# UNO_Mega_IO.net
KiCad netlist of a schematic drawn in Altium Designer
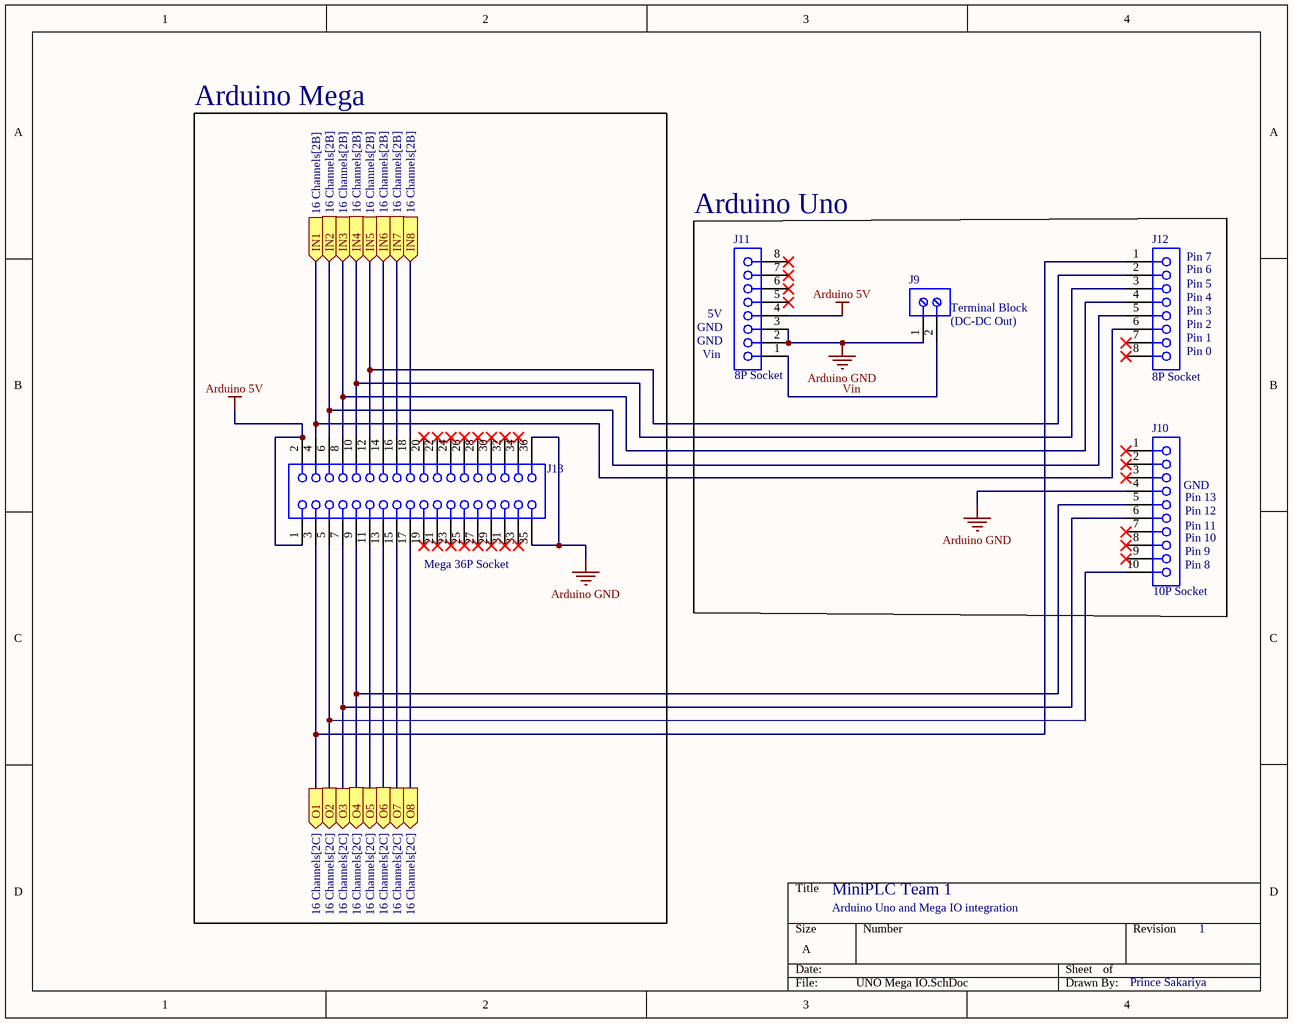
[diagram p0: UNO Mega IO.SchDoc]

(export (version "E")
  (design (tool "Eeschema 10.0.6"))
  (components
    (comp (ref "J9")
      (value "Terminal Block")
      (footprint "691103110002")
      (fields (field (name "VOLTAGE") "125V"))
      (libsource (lib "Altium Content Vault") (part "TBL - 1R - 02P - Screw"))
    )
    (comp (ref "J10")
      (value "10P Socket")
      (footprint "61301011821")
      (libsource (lib "Altium Content Vault") (part "Header_Female_1R_10P"))
    )
    (comp (ref "J11")
      (value "8P Socket")
      (footprint "61300811821")
      (libsource (lib "Altium Content Vault") (part "Header_Female_1R_08P"))
    )
    (comp (ref "J12")
      (value "8P Socket")
      (footprint "61300811821")
      (libsource (lib "Altium Content Vault") (part "Header_Female_1R_08P"))
    )
    (comp (ref "J13")
      (value "Mega 36P Socket")
      (footprint "61303621821")
      (libsource (lib "Altium Content Vault") (part "Header_Female_2R_36P"))
    )
  )
  (nets
    (net (code "1") (name "/IN1") (class "Default")
      (node (ref "J12") (pin "6") (pinfunction "6_6") (pintype "passive"))
      (node (ref "J13") (pin "4") (pinfunction "4_4") (pintype "passive"))
    )
    (net (code "2") (name "/IN2") (class "Default")
      (node (ref "J12") (pin "5") (pinfunction "5_5") (pintype "passive"))
      (node (ref "J13") (pin "6") (pinfunction "6_6") (pintype "passive"))
    )
    (net (code "3") (name "/IN3") (class "Default")
      (node (ref "J12") (pin "4") (pinfunction "4_4") (pintype "passive"))
      (node (ref "J13") (pin "8") (pinfunction "8_8") (pintype "passive"))
    )
    (net (code "4") (name "/IN4") (class "Default")
      (node (ref "J12") (pin "3") (pinfunction "3_3") (pintype "passive"))
      (node (ref "J13") (pin "10") (pinfunction "10_10") (pintype "passive"))
    )
    (net (code "5") (name "/IN5") (class "Default")
      (node (ref "J12") (pin "2") (pinfunction "2_2") (pintype "passive"))
      (node (ref "J13") (pin "12") (pinfunction "12_12") (pintype "passive"))
    )
    (net (code "6") (name "/IN6") (class "Default")
      (node (ref "J13") (pin "14") (pinfunction "14_14") (pintype "passive"))
    )
    (net (code "7") (name "/IN7") (class "Default")
      (node (ref "J13") (pin "16") (pinfunction "16_16") (pintype "passive"))
    )
    (net (code "8") (name "/IN8") (class "Default")
      (node (ref "J13") (pin "18") (pinfunction "18_18") (pintype "passive"))
    )
    (net (code "9") (name "/O1") (class "Default")
      (node (ref "J12") (pin "1") (pinfunction "1_1") (pintype "passive"))
      (node (ref "J13") (pin "3") (pinfunction "3_3") (pintype "passive"))
    )
    (net (code "10") (name "/O2") (class "Default")
      (node (ref "J10") (pin "10") (pinfunction "10_10") (pintype "passive"))
      (node (ref "J13") (pin "5") (pinfunction "5_5") (pintype "passive"))
    )
    (net (code "11") (name "/O3") (class "Default")
      (node (ref "J10") (pin "6") (pinfunction "6_6") (pintype "passive"))
      (node (ref "J13") (pin "7") (pinfunction "7_7") (pintype "passive"))
    )
    (net (code "12") (name "/O4") (class "Default")
      (node (ref "J10") (pin "5") (pinfunction "5_5") (pintype "passive"))
      (node (ref "J13") (pin "9") (pinfunction "9_9") (pintype "passive"))
    )
    (net (code "13") (name "/O5") (class "Default")
      (node (ref "J13") (pin "11") (pinfunction "11_11") (pintype "passive"))
    )
    (net (code "14") (name "/O6") (class "Default")
      (node (ref "J13") (pin "13") (pinfunction "13_13") (pintype "passive"))
    )
    (net (code "15") (name "/O7") (class "Default")
      (node (ref "J13") (pin "15") (pinfunction "15_15") (pintype "passive"))
    )
    (net (code "16") (name "/O8") (class "Default")
      (node (ref "J13") (pin "17") (pinfunction "17_17") (pintype "passive"))
    )
    (net (code "17") (name "/Vin") (class "Default")
      (node (ref "J11") (pin "1") (pinfunction "1_1") (pintype "passive"))
      (node (ref "J9") (pin "2") (pinfunction "2_2") (pintype "passive"))
    )
    (net (code "18") (name "Arduino 5V") (class "Default")
      (node (ref "J11") (pin "4") (pinfunction "4_4") (pintype "passive"))
      (node (ref "J13") (pin "1") (pinfunction "1_1") (pintype "passive"))
      (node (ref "J13") (pin "2") (pinfunction "2_2") (pintype "passive"))
    )
    (net (code "19") (name "Arduino GND") (class "Default")
      (node (ref "J10") (pin "4") (pinfunction "4_4") (pintype "passive"))
      (node (ref "J11") (pin "2") (pinfunction "2_2") (pintype "passive"))
      (node (ref "J11") (pin "3") (pinfunction "3_3") (pintype "passive"))
      (node (ref "J13") (pin "35") (pinfunction "35_35") (pintype "passive"))
      (node (ref "J13") (pin "36") (pinfunction "36_36") (pintype "passive"))
      (node (ref "J9") (pin "1") (pinfunction "1_1") (pintype "passive"))
    )
    (net (code "20") (name "unconnected-(J10-Pad1)") (class "Default")
      (node (ref "J10") (pin "1") (pinfunction "1_1") (pintype "passive+no_connect"))
    )
    (net (code "21") (name "unconnected-(J10-Pad2)") (class "Default")
      (node (ref "J10") (pin "2") (pinfunction "2_2") (pintype "passive+no_connect"))
    )
    (net (code "22") (name "unconnected-(J10-Pad3)") (class "Default")
      (node (ref "J10") (pin "3") (pinfunction "3_3") (pintype "passive+no_connect"))
    )
    (net (code "23") (name "unconnected-(J10-Pad7)") (class "Default")
      (node (ref "J10") (pin "7") (pinfunction "7_7") (pintype "passive+no_connect"))
    )
    (net (code "24") (name "unconnected-(J10-Pad8)") (class "Default")
      (node (ref "J10") (pin "8") (pinfunction "8_8") (pintype "passive+no_connect"))
    )
    (net (code "25") (name "unconnected-(J10-Pad9)") (class "Default")
      (node (ref "J10") (pin "9") (pinfunction "9_9") (pintype "passive+no_connect"))
    )
    (net (code "26") (name "unconnected-(J11-Pad5)") (class "Default")
      (node (ref "J11") (pin "5") (pinfunction "5_5") (pintype "passive+no_connect"))
    )
    (net (code "27") (name "unconnected-(J11-Pad6)") (class "Default")
      (node (ref "J11") (pin "6") (pinfunction "6_6") (pintype "passive+no_connect"))
    )
    (net (code "28") (name "unconnected-(J11-Pad7)") (class "Default")
      (node (ref "J11") (pin "7") (pinfunction "7_7") (pintype "passive+no_connect"))
    )
    (net (code "29") (name "unconnected-(J11-Pad8)") (class "Default")
      (node (ref "J11") (pin "8") (pinfunction "8_8") (pintype "passive+no_connect"))
    )
    (net (code "30") (name "unconnected-(J12-Pad7)") (class "Default")
      (node (ref "J12") (pin "7") (pinfunction "7_7") (pintype "passive+no_connect"))
    )
    (net (code "31") (name "unconnected-(J12-Pad8)") (class "Default")
      (node (ref "J12") (pin "8") (pinfunction "8_8") (pintype "passive+no_connect"))
    )
    (net (code "32") (name "unconnected-(J13-Pad19)") (class "Default")
      (node (ref "J13") (pin "19") (pinfunction "19_19") (pintype "passive+no_connect"))
    )
    (net (code "33") (name "unconnected-(J13-Pad20)") (class "Default")
      (node (ref "J13") (pin "20") (pinfunction "20_20") (pintype "passive+no_connect"))
    )
    (net (code "34") (name "unconnected-(J13-Pad21)") (class "Default")
      (node (ref "J13") (pin "21") (pinfunction "21_21") (pintype "passive+no_connect"))
    )
    (net (code "35") (name "unconnected-(J13-Pad22)") (class "Default")
      (node (ref "J13") (pin "22") (pinfunction "22_22") (pintype "passive+no_connect"))
    )
    (net (code "36") (name "unconnected-(J13-Pad23)") (class "Default")
      (node (ref "J13") (pin "23") (pinfunction "23_23") (pintype "passive+no_connect"))
    )
    (net (code "37") (name "unconnected-(J13-Pad24)") (class "Default")
      (node (ref "J13") (pin "24") (pinfunction "24_24") (pintype "passive+no_connect"))
    )
    (net (code "38") (name "unconnected-(J13-Pad25)") (class "Default")
      (node (ref "J13") (pin "25") (pinfunction "25_25") (pintype "passive+no_connect"))
    )
    (net (code "39") (name "unconnected-(J13-Pad26)") (class "Default")
      (node (ref "J13") (pin "26") (pinfunction "26_26") (pintype "passive+no_connect"))
    )
    (net (code "40") (name "unconnected-(J13-Pad27)") (class "Default")
      (node (ref "J13") (pin "27") (pinfunction "27_27") (pintype "passive+no_connect"))
    )
    (net (code "41") (name "unconnected-(J13-Pad28)") (class "Default")
      (node (ref "J13") (pin "28") (pinfunction "28_28") (pintype "passive+no_connect"))
    )
    (net (code "42") (name "unconnected-(J13-Pad29)") (class "Default")
      (node (ref "J13") (pin "29") (pinfunction "29_29") (pintype "passive+no_connect"))
    )
    (net (code "43") (name "unconnected-(J13-Pad30)") (class "Default")
      (node (ref "J13") (pin "30") (pinfunction "30_30") (pintype "passive+no_connect"))
    )
    (net (code "44") (name "unconnected-(J13-Pad31)") (class "Default")
      (node (ref "J13") (pin "31") (pinfunction "31_31") (pintype "passive+no_connect"))
    )
    (net (code "45") (name "unconnected-(J13-Pad32)") (class "Default")
      (node (ref "J13") (pin "32") (pinfunction "32_32") (pintype "passive+no_connect"))
    )
    (net (code "46") (name "unconnected-(J13-Pad33)") (class "Default")
      (node (ref "J13") (pin "33") (pinfunction "33_33") (pintype "passive+no_connect"))
    )
    (net (code "47") (name "unconnected-(J13-Pad34)") (class "Default")
      (node (ref "J13") (pin "34") (pinfunction "34_34") (pintype "passive+no_connect"))
    )
  )
)
